# SWITCHBOARD3.net
KiCad netlist of a schematic drawn in EAGLE
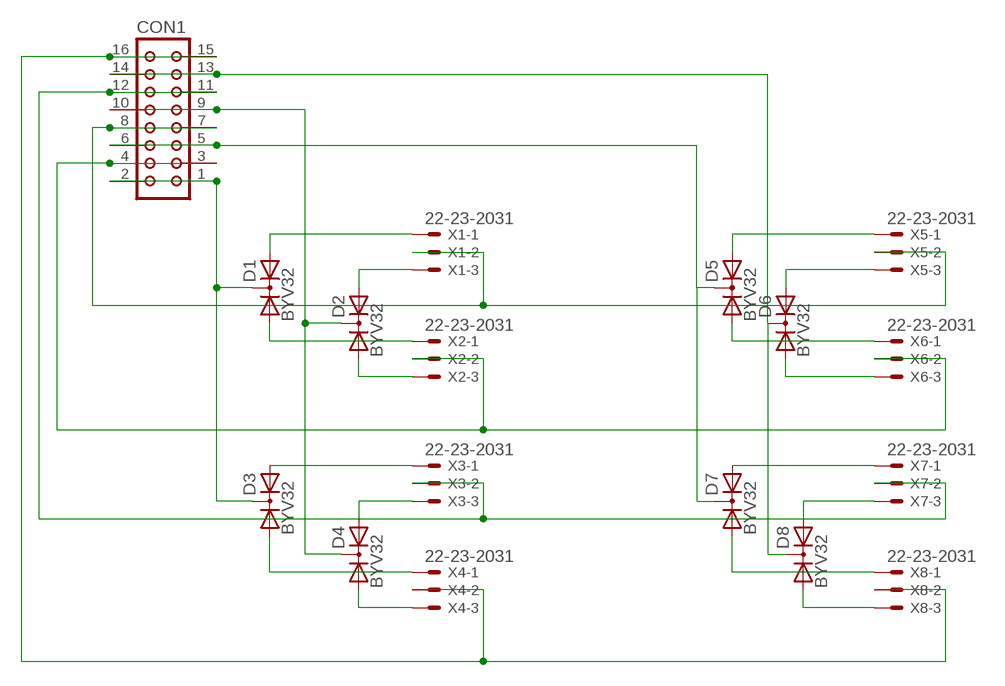
[diagram p0: schematic, sheet 1]

(export (version "E")
  (design (tool "Eeschema 10.0.6"))
  (components
    (comp (ref "CON1")
      (value "CON16")
      (footprint "eagle-import:CON16")
      (libsource (lib "eagle-import") (part "CON16"))
    )
    (comp (ref "D1")
      (value "BYV32")
      (footprint "eagle-import:TO220ABS")
      (libsource (lib "eagle-import") (part "BYV32"))
    )
    (comp (ref "D2")
      (value "BYV32")
      (footprint "eagle-import:TO220ABS")
      (libsource (lib "eagle-import") (part "BYV32"))
    )
    (comp (ref "D3")
      (value "BYV32")
      (footprint "eagle-import:TO220ABS")
      (libsource (lib "eagle-import") (part "BYV32"))
    )
    (comp (ref "D4")
      (value "BYV32")
      (footprint "eagle-import:TO220ABS")
      (libsource (lib "eagle-import") (part "BYV32"))
    )
    (comp (ref "D5")
      (value "BYV32")
      (footprint "eagle-import:TO220ABS")
      (libsource (lib "eagle-import") (part "BYV32"))
    )
    (comp (ref "D6")
      (value "BYV32")
      (footprint "eagle-import:TO220ABS")
      (libsource (lib "eagle-import") (part "BYV32"))
    )
    (comp (ref "D7")
      (value "BYV32")
      (footprint "eagle-import:TO220ABS")
      (libsource (lib "eagle-import") (part "BYV32"))
    )
    (comp (ref "D8")
      (value "BYV32")
      (footprint "eagle-import:TO220ABS")
      (libsource (lib "eagle-import") (part "BYV32"))
    )
    (comp (ref "X1")
      (value "22-23-2031")
      (footprint "eagle-import:22-23-2031")
      (fields (field (name "MF") "MOLEX"))
      (libsource (lib "eagle-import") (part "22-23-2031"))
    )
    (comp (ref "X2")
      (value "22-23-2031")
      (footprint "eagle-import:22-23-2031")
      (fields (field (name "MF") "MOLEX"))
      (libsource (lib "eagle-import") (part "22-23-2031"))
    )
    (comp (ref "X3")
      (value "22-23-2031")
      (footprint "eagle-import:22-23-2031")
      (fields (field (name "MF") "MOLEX"))
      (libsource (lib "eagle-import") (part "22-23-2031"))
    )
    (comp (ref "X4")
      (value "22-23-2031")
      (footprint "eagle-import:22-23-2031")
      (fields (field (name "MF") "MOLEX"))
      (libsource (lib "eagle-import") (part "22-23-2031"))
    )
    (comp (ref "X5")
      (value "22-23-2031")
      (footprint "eagle-import:22-23-2031")
      (fields (field (name "MF") "MOLEX"))
      (libsource (lib "eagle-import") (part "22-23-2031"))
    )
    (comp (ref "X6")
      (value "22-23-2031")
      (footprint "eagle-import:22-23-2031")
      (fields (field (name "MF") "MOLEX"))
      (libsource (lib "eagle-import") (part "22-23-2031"))
    )
    (comp (ref "X7")
      (value "22-23-2031")
      (footprint "eagle-import:22-23-2031")
      (fields (field (name "MF") "MOLEX"))
      (libsource (lib "eagle-import") (part "22-23-2031"))
    )
    (comp (ref "X8")
      (value "22-23-2031")
      (footprint "eagle-import:22-23-2031")
      (fields (field (name "MF") "MOLEX"))
      (libsource (lib "eagle-import") (part "22-23-2031"))
    )
  )
  (nets
    (net (code "1") (name "Net-(CON1-Pad1)") (class "Default")
      (node (ref "CON1") (pin "1") (pinfunction "1_1") (pintype "passive"))
      (node (ref "CON1") (pin "2") (pinfunction "2_2") (pintype "passive"))
      (node (ref "D1") (pin "C") (pinfunction "C_C") (pintype "passive"))
      (node (ref "D3") (pin "C") (pinfunction "C_C") (pintype "passive"))
    )
    (net (code "2") (name "Net-(CON1-Pad5)") (class "Default")
      (node (ref "CON1") (pin "5") (pinfunction "5_5") (pintype "passive"))
      (node (ref "CON1") (pin "6") (pinfunction "6_6") (pintype "passive"))
      (node (ref "D5") (pin "C") (pinfunction "C_C") (pintype "passive"))
      (node (ref "D7") (pin "C") (pinfunction "C_C") (pintype "passive"))
    )
    (net (code "3") (name "Net-(CON1-Pad10)") (class "Default")
      (node (ref "CON1") (pin "10") (pinfunction "10_10") (pintype "passive"))
      (node (ref "CON1") (pin "9") (pinfunction "9_9") (pintype "passive"))
      (node (ref "D2") (pin "C") (pinfunction "C_C") (pintype "passive"))
      (node (ref "D4") (pin "C") (pinfunction "C_C") (pintype "passive"))
    )
    (net (code "4") (name "Net-(CON1-Pad13)") (class "Default")
      (node (ref "CON1") (pin "13") (pinfunction "13_13") (pintype "passive"))
      (node (ref "CON1") (pin "14") (pinfunction "14_14") (pintype "passive"))
      (node (ref "D6") (pin "C") (pinfunction "C_C") (pintype "passive"))
      (node (ref "D8") (pin "C") (pinfunction "C_C") (pintype "passive"))
    )
    (net (code "5") (name "Net-(X1A-S)") (class "Default")
      (node (ref "D1") (pin "A2") (pinfunction "A2_A2") (pintype "passive"))
      (node (ref "X1") (pin "1") (pinfunction "S_1") (pintype "passive"))
    )
    (net (code "6") (name "Net-(X1B-S)") (class "Default")
      (node (ref "CON1") (pin "7") (pinfunction "7_7") (pintype "passive"))
      (node (ref "CON1") (pin "8") (pinfunction "8_8") (pintype "passive"))
      (node (ref "X1") (pin "2") (pinfunction "S_2") (pintype "passive"))
      (node (ref "X5") (pin "2") (pinfunction "S_2") (pintype "passive"))
    )
    (net (code "7") (name "Net-(X1C-S)") (class "Default")
      (node (ref "D2") (pin "A2") (pinfunction "A2_A2") (pintype "passive"))
      (node (ref "X1") (pin "3") (pinfunction "S_3") (pintype "passive"))
    )
    (net (code "8") (name "Net-(X2A-S)") (class "Default")
      (node (ref "D1") (pin "A1") (pinfunction "A1_A1") (pintype "passive"))
      (node (ref "X2") (pin "1") (pinfunction "S_1") (pintype "passive"))
    )
    (net (code "9") (name "Net-(X2B-S)") (class "Default")
      (node (ref "CON1") (pin "3") (pinfunction "3_3") (pintype "passive"))
      (node (ref "CON1") (pin "4") (pinfunction "4_4") (pintype "passive"))
      (node (ref "X2") (pin "2") (pinfunction "S_2") (pintype "passive"))
      (node (ref "X6") (pin "2") (pinfunction "S_2") (pintype "passive"))
    )
    (net (code "10") (name "Net-(X2C-S)") (class "Default")
      (node (ref "D2") (pin "A1") (pinfunction "A1_A1") (pintype "passive"))
      (node (ref "X2") (pin "3") (pinfunction "S_3") (pintype "passive"))
    )
    (net (code "11") (name "Net-(X3A-S)") (class "Default")
      (node (ref "D3") (pin "A2") (pinfunction "A2_A2") (pintype "passive"))
      (node (ref "X3") (pin "1") (pinfunction "S_1") (pintype "passive"))
    )
    (net (code "12") (name "Net-(X3B-S)") (class "Default")
      (node (ref "CON1") (pin "11") (pinfunction "11_11") (pintype "passive"))
      (node (ref "CON1") (pin "12") (pinfunction "12_12") (pintype "passive"))
      (node (ref "X3") (pin "2") (pinfunction "S_2") (pintype "passive"))
      (node (ref "X7") (pin "2") (pinfunction "S_2") (pintype "passive"))
    )
    (net (code "13") (name "Net-(X3C-S)") (class "Default")
      (node (ref "D4") (pin "A2") (pinfunction "A2_A2") (pintype "passive"))
      (node (ref "X3") (pin "3") (pinfunction "S_3") (pintype "passive"))
    )
    (net (code "14") (name "Net-(X4A-S)") (class "Default")
      (node (ref "D3") (pin "A1") (pinfunction "A1_A1") (pintype "passive"))
      (node (ref "X4") (pin "1") (pinfunction "S_1") (pintype "passive"))
    )
    (net (code "15") (name "Net-(X4B-S)") (class "Default")
      (node (ref "CON1") (pin "15") (pinfunction "15_15") (pintype "passive"))
      (node (ref "CON1") (pin "16") (pinfunction "16_16") (pintype "passive"))
      (node (ref "X4") (pin "2") (pinfunction "S_2") (pintype "passive"))
      (node (ref "X8") (pin "2") (pinfunction "S_2") (pintype "passive"))
    )
    (net (code "16") (name "Net-(X4C-S)") (class "Default")
      (node (ref "D4") (pin "A1") (pinfunction "A1_A1") (pintype "passive"))
      (node (ref "X4") (pin "3") (pinfunction "S_3") (pintype "passive"))
    )
    (net (code "17") (name "Net-(X5A-S)") (class "Default")
      (node (ref "D5") (pin "A2") (pinfunction "A2_A2") (pintype "passive"))
      (node (ref "X5") (pin "1") (pinfunction "S_1") (pintype "passive"))
    )
    (net (code "18") (name "Net-(X5C-S)") (class "Default")
      (node (ref "D6") (pin "A2") (pinfunction "A2_A2") (pintype "passive"))
      (node (ref "X5") (pin "3") (pinfunction "S_3") (pintype "passive"))
    )
    (net (code "19") (name "Net-(X6A-S)") (class "Default")
      (node (ref "D5") (pin "A1") (pinfunction "A1_A1") (pintype "passive"))
      (node (ref "X6") (pin "1") (pinfunction "S_1") (pintype "passive"))
    )
    (net (code "20") (name "Net-(X6C-S)") (class "Default")
      (node (ref "D6") (pin "A1") (pinfunction "A1_A1") (pintype "passive"))
      (node (ref "X6") (pin "3") (pinfunction "S_3") (pintype "passive"))
    )
    (net (code "21") (name "Net-(X7A-S)") (class "Default")
      (node (ref "D7") (pin "A2") (pinfunction "A2_A2") (pintype "passive"))
      (node (ref "X7") (pin "1") (pinfunction "S_1") (pintype "passive"))
    )
    (net (code "22") (name "Net-(X7C-S)") (class "Default")
      (node (ref "D8") (pin "A2") (pinfunction "A2_A2") (pintype "passive"))
      (node (ref "X7") (pin "3") (pinfunction "S_3") (pintype "passive"))
    )
    (net (code "23") (name "Net-(X8A-S)") (class "Default")
      (node (ref "D7") (pin "A1") (pinfunction "A1_A1") (pintype "passive"))
      (node (ref "X8") (pin "1") (pinfunction "S_1") (pintype "passive"))
    )
    (net (code "24") (name "Net-(X8C-S)") (class "Default")
      (node (ref "D8") (pin "A1") (pinfunction "A1_A1") (pintype "passive"))
      (node (ref "X8") (pin "3") (pinfunction "S_3") (pintype "passive"))
    )
  )
)
